# WirelessTallyReceiver.net
KiCad netlist of a schematic drawn in EAGLE
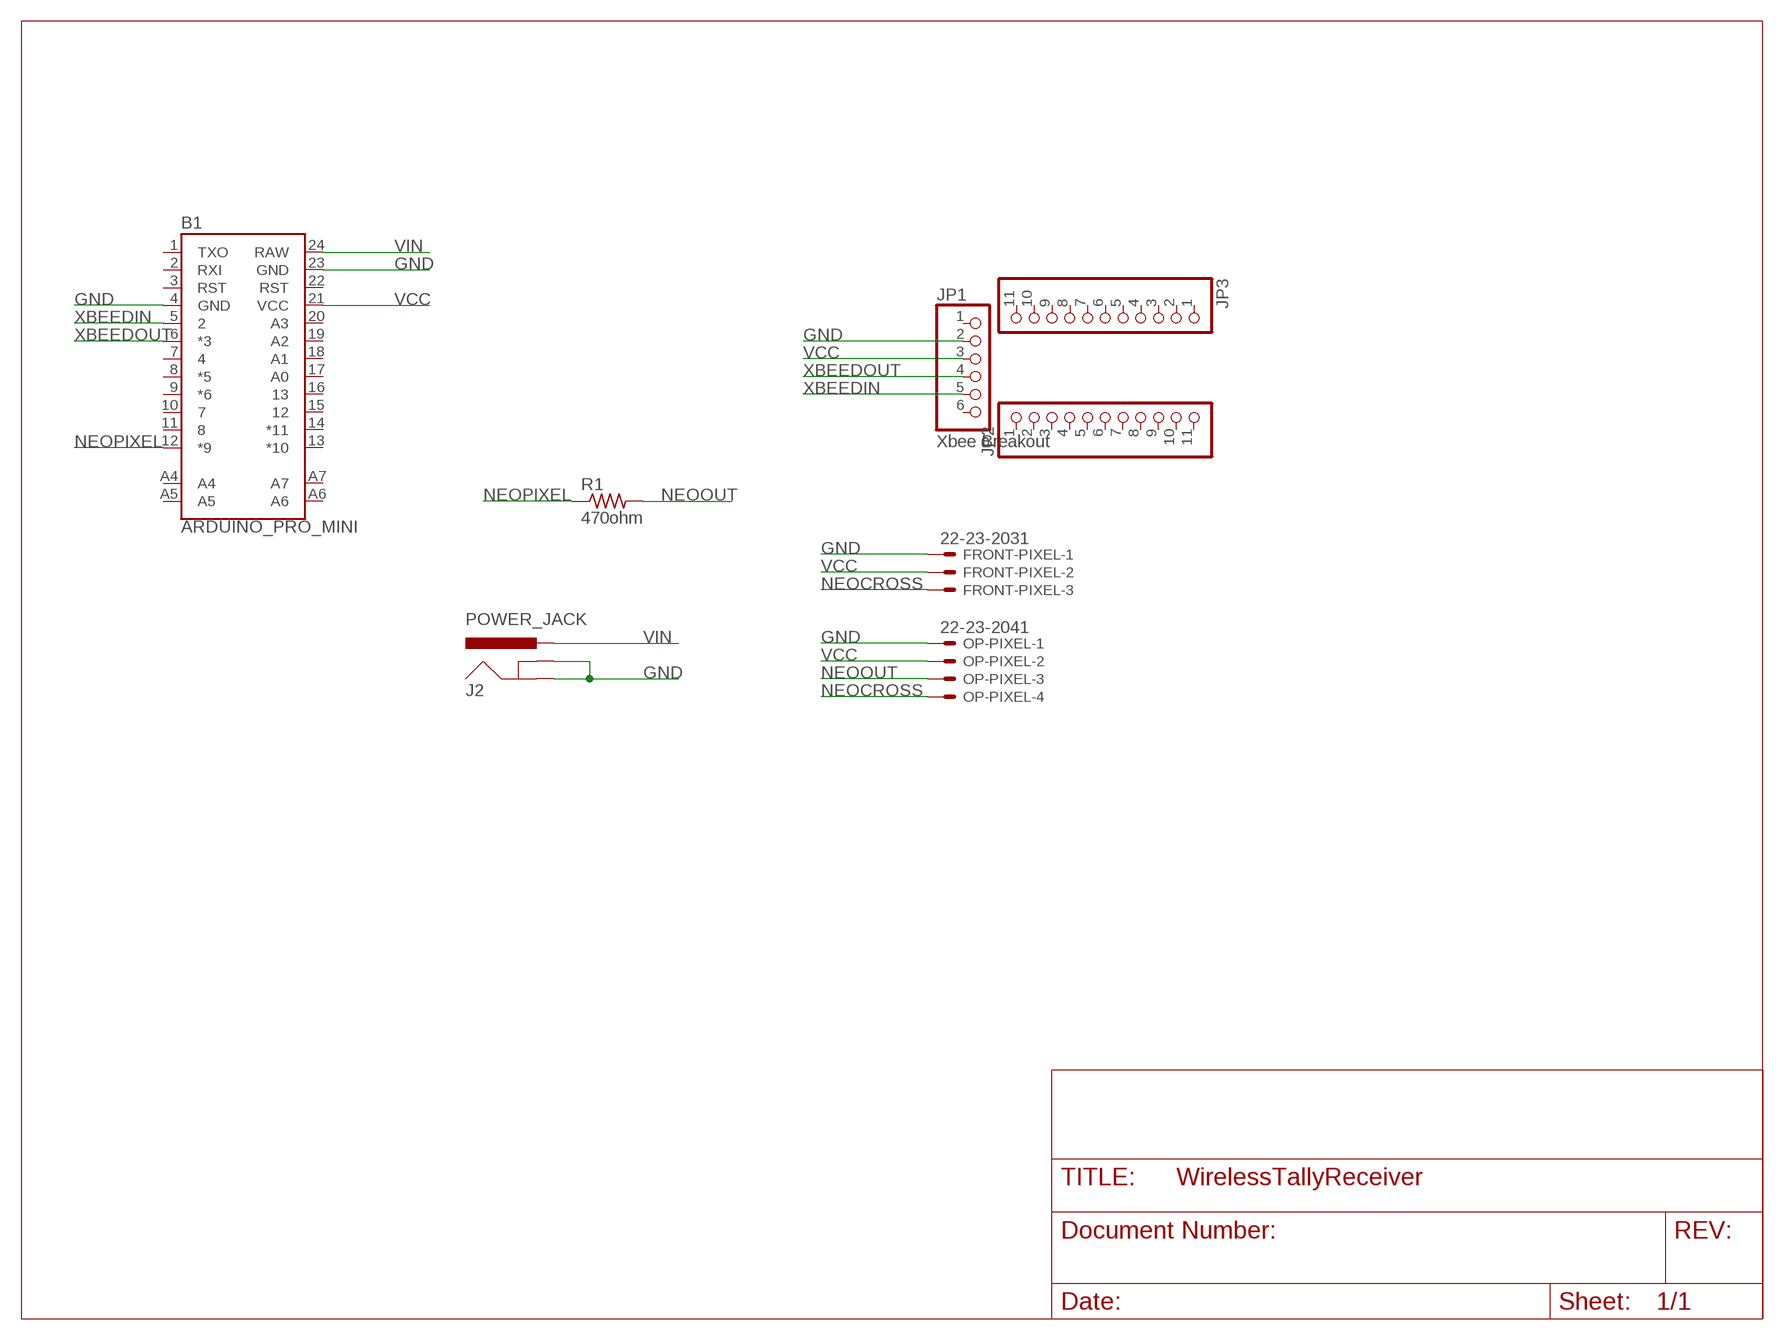
[diagram p0: schematic, sheet 1]

(export (version "E")
  (design (tool "Eeschema 10.0.6"))
  (components
    (comp (ref "B1")
      (value "ARDUINO_PRO_MINI")
      (footprint "eagle-import:ARDUINO_PRO_MINI")
      (libsource (lib "eagle-import") (part "ARDUINO_PRO_MINI"))
    )
    (comp (ref "FRONT-PIXEL")
      (value "22-23-2031")
      (footprint "eagle-import:22-23-2031")
      (fields (field (name "MF") "MOLEX"))
      (libsource (lib "eagle-import") (part "22-23-2031"))
    )
    (comp (ref "J2")
      (value "POWER_JACK")
      (footprint "eagle-import:POWER_JACK_PTH")
      (libsource (lib "eagle-import") (part "POWER_JACK"))
    )
    (comp (ref "JP1")
      (value "Xbee Breakout")
      (footprint "eagle-import:1X06")
      (libsource (lib "eagle-import") (part "PINHD-1X6"))
    )
    (comp (ref "JP2")
      (value "PINHD-1X11")
      (footprint "eagle-import:1X11")
      (libsource (lib "eagle-import") (part "PINHD-1X11"))
    )
    (comp (ref "JP3")
      (value "PINHD-1X11")
      (footprint "eagle-import:1X11")
      (libsource (lib "eagle-import") (part "PINHD-1X11"))
    )
    (comp (ref "OP-PIXEL")
      (value "22-23-2041")
      (footprint "eagle-import:22-23-2041")
      (fields (field (name "MF") "MOLEX"))
      (libsource (lib "eagle-import") (part "22-23-2041"))
    )
    (comp (ref "R1")
      (value "470ohm")
      (footprint "eagle-import:R0805")
      (libsource (lib "eagle-import") (part "R-US_R0805"))
    )
  )
  (nets
    (net (code "1") (name "/GND") (class "Default")
      (node (ref "B1") (pin "23") (pinfunction "GND_23") (pintype "power_in"))
      (node (ref "B1") (pin "4") (pinfunction "GND_4") (pintype "power_in"))
      (node (ref "FRONT-PIXEL") (pin "1") (pinfunction "S_1") (pintype "passive"))
      (node (ref "J2") (pin "GND") (pinfunction "GND_GND") (pintype "bidirectional"))
      (node (ref "J2") (pin "GNDBREAK") (pinfunction "GNDBREAK_GNDBREAK") (pintype "bidirectional"))
      (node (ref "JP1") (pin "2") (pinfunction "2_2") (pintype "passive"))
      (node (ref "OP-PIXEL") (pin "1") (pinfunction "S_1") (pintype "passive"))
    )
    (net (code "2") (name "/NEOCROSS") (class "Default")
      (node (ref "FRONT-PIXEL") (pin "3") (pinfunction "S_3") (pintype "passive"))
      (node (ref "OP-PIXEL") (pin "4") (pinfunction "S_4") (pintype "passive"))
    )
    (net (code "3") (name "/NEOOUT") (class "Default")
      (node (ref "OP-PIXEL") (pin "3") (pinfunction "S_3") (pintype "passive"))
      (node (ref "R1") (pin "2") (pinfunction "2_2") (pintype "passive"))
    )
    (net (code "4") (name "/NEOPIXEL") (class "Default")
      (node (ref "B1") (pin "12") (pinfunction "*9_12") (pintype "bidirectional"))
      (node (ref "R1") (pin "1") (pinfunction "1_1") (pintype "passive"))
    )
    (net (code "5") (name "/VCC") (class "Default")
      (node (ref "B1") (pin "21") (pinfunction "VCC_21") (pintype "power_in"))
      (node (ref "FRONT-PIXEL") (pin "2") (pinfunction "S_2") (pintype "passive"))
      (node (ref "JP1") (pin "3") (pinfunction "3_3") (pintype "passive"))
      (node (ref "OP-PIXEL") (pin "2") (pinfunction "S_2") (pintype "passive"))
    )
    (net (code "6") (name "/VIN") (class "Default")
      (node (ref "B1") (pin "24") (pinfunction "RAW_24") (pintype "power_in"))
      (node (ref "J2") (pin "PWR") (pinfunction "PWR_PWR") (pintype "bidirectional"))
    )
    (net (code "7") (name "/XBEEDIN") (class "Default")
      (node (ref "B1") (pin "5") (pinfunction "2_5") (pintype "bidirectional"))
      (node (ref "JP1") (pin "5") (pinfunction "5_5") (pintype "passive"))
    )
    (net (code "8") (name "/XBEEDOUT") (class "Default")
      (node (ref "B1") (pin "6") (pinfunction "*3_6") (pintype "bidirectional"))
      (node (ref "JP1") (pin "4") (pinfunction "4_4") (pintype "passive"))
    )
    (net (code "9") (name "unconnected-(B1-*5-Pad8)") (class "Default")
      (node (ref "B1") (pin "8") (pinfunction "*5_8") (pintype "bidirectional"))
    )
    (net (code "10") (name "unconnected-(B1-*6-Pad9)") (class "Default")
      (node (ref "B1") (pin "9") (pinfunction "*6_9") (pintype "bidirectional"))
    )
    (net (code "11") (name "unconnected-(B1-*10-Pad13)") (class "Default")
      (node (ref "B1") (pin "13") (pinfunction "*10_13") (pintype "bidirectional"))
    )
    (net (code "12") (name "unconnected-(B1-*11-Pad14)") (class "Default")
      (node (ref "B1") (pin "14") (pinfunction "*11_14") (pintype "bidirectional"))
    )
    (net (code "13") (name "unconnected-(B1-4-Pad7)") (class "Default")
      (node (ref "B1") (pin "7") (pinfunction "4_7") (pintype "bidirectional"))
    )
    (net (code "14") (name "unconnected-(B1-7-Pad10)") (class "Default")
      (node (ref "B1") (pin "10") (pinfunction "7_10") (pintype "bidirectional"))
    )
    (net (code "15") (name "unconnected-(B1-8-Pad11)") (class "Default")
      (node (ref "B1") (pin "11") (pinfunction "8_11") (pintype "bidirectional"))
    )
    (net (code "16") (name "unconnected-(B1-12-Pad15)") (class "Default")
      (node (ref "B1") (pin "15") (pinfunction "12_15") (pintype "bidirectional"))
    )
    (net (code "17") (name "unconnected-(B1-13-Pad16)") (class "Default")
      (node (ref "B1") (pin "16") (pinfunction "13_16") (pintype "bidirectional"))
    )
    (net (code "18") (name "unconnected-(B1-A0-Pad17)") (class "Default")
      (node (ref "B1") (pin "17") (pinfunction "A0_17") (pintype "bidirectional"))
    )
    (net (code "19") (name "unconnected-(B1-A1-Pad18)") (class "Default")
      (node (ref "B1") (pin "18") (pinfunction "A1_18") (pintype "bidirectional"))
    )
    (net (code "20") (name "unconnected-(B1-A2-Pad19)") (class "Default")
      (node (ref "B1") (pin "19") (pinfunction "A2_19") (pintype "bidirectional"))
    )
    (net (code "21") (name "unconnected-(B1-A3-Pad20)") (class "Default")
      (node (ref "B1") (pin "20") (pinfunction "A3_20") (pintype "bidirectional"))
    )
    (net (code "22") (name "unconnected-(B1-PadA4)") (class "Default")
      (node (ref "B1") (pin "A4") (pinfunction "A4_A4") (pintype "bidirectional"))
    )
    (net (code "23") (name "unconnected-(B1-PadA5)") (class "Default")
      (node (ref "B1") (pin "A5") (pinfunction "A5_A5") (pintype "bidirectional"))
    )
    (net (code "24") (name "unconnected-(B1-PadA6)") (class "Default")
      (node (ref "B1") (pin "A6") (pinfunction "A6_A6") (pintype "bidirectional"))
    )
    (net (code "25") (name "unconnected-(B1-PadA7)") (class "Default")
      (node (ref "B1") (pin "A7") (pinfunction "A7_A7") (pintype "bidirectional"))
    )
    (net (code "26") (name "unconnected-(B1-RST-Pad3)") (class "Default")
      (node (ref "B1") (pin "3") (pinfunction "RST_3") (pintype "bidirectional"))
    )
    (net (code "27") (name "unconnected-(B1-RST-Pad22)") (class "Default")
      (node (ref "B1") (pin "22") (pinfunction "RST_22") (pintype "bidirectional"))
    )
    (net (code "28") (name "unconnected-(B1-RXI-Pad2)") (class "Default")
      (node (ref "B1") (pin "2") (pinfunction "RXI_2") (pintype "bidirectional"))
    )
    (net (code "29") (name "unconnected-(B1-TXO-Pad1)") (class "Default")
      (node (ref "B1") (pin "1") (pinfunction "TXO_1") (pintype "bidirectional"))
    )
    (net (code "30") (name "unconnected-(JP1-Pad1)") (class "Default")
      (node (ref "JP1") (pin "1") (pinfunction "1_1") (pintype "passive"))
    )
    (net (code "31") (name "unconnected-(JP1-Pad6)") (class "Default")
      (node (ref "JP1") (pin "6") (pinfunction "6_6") (pintype "passive"))
    )
    (net (code "32") (name "unconnected-(JP2-Pad1)") (class "Default")
      (node (ref "JP2") (pin "1") (pinfunction "1_1") (pintype "passive"))
    )
    (net (code "33") (name "unconnected-(JP2-Pad2)") (class "Default")
      (node (ref "JP2") (pin "2") (pinfunction "2_2") (pintype "passive"))
    )
    (net (code "34") (name "unconnected-(JP2-Pad3)") (class "Default")
      (node (ref "JP2") (pin "3") (pinfunction "3_3") (pintype "passive"))
    )
    (net (code "35") (name "unconnected-(JP2-Pad4)") (class "Default")
      (node (ref "JP2") (pin "4") (pinfunction "4_4") (pintype "passive"))
    )
    (net (code "36") (name "unconnected-(JP2-Pad5)") (class "Default")
      (node (ref "JP2") (pin "5") (pinfunction "5_5") (pintype "passive"))
    )
    (net (code "37") (name "unconnected-(JP2-Pad6)") (class "Default")
      (node (ref "JP2") (pin "6") (pinfunction "6_6") (pintype "passive"))
    )
    (net (code "38") (name "unconnected-(JP2-Pad7)") (class "Default")
      (node (ref "JP2") (pin "7") (pinfunction "7_7") (pintype "passive"))
    )
    (net (code "39") (name "unconnected-(JP2-Pad8)") (class "Default")
      (node (ref "JP2") (pin "8") (pinfunction "8_8") (pintype "passive"))
    )
    (net (code "40") (name "unconnected-(JP2-Pad9)") (class "Default")
      (node (ref "JP2") (pin "9") (pinfunction "9_9") (pintype "passive"))
    )
    (net (code "41") (name "unconnected-(JP2-Pad10)") (class "Default")
      (node (ref "JP2") (pin "10") (pinfunction "10_10") (pintype "passive"))
    )
    (net (code "42") (name "unconnected-(JP2-Pad11)") (class "Default")
      (node (ref "JP2") (pin "11") (pinfunction "11_11") (pintype "passive"))
    )
    (net (code "43") (name "unconnected-(JP3-Pad1)") (class "Default")
      (node (ref "JP3") (pin "1") (pinfunction "1_1") (pintype "passive"))
    )
    (net (code "44") (name "unconnected-(JP3-Pad2)") (class "Default")
      (node (ref "JP3") (pin "2") (pinfunction "2_2") (pintype "passive"))
    )
    (net (code "45") (name "unconnected-(JP3-Pad3)") (class "Default")
      (node (ref "JP3") (pin "3") (pinfunction "3_3") (pintype "passive"))
    )
    (net (code "46") (name "unconnected-(JP3-Pad4)") (class "Default")
      (node (ref "JP3") (pin "4") (pinfunction "4_4") (pintype "passive"))
    )
    (net (code "47") (name "unconnected-(JP3-Pad5)") (class "Default")
      (node (ref "JP3") (pin "5") (pinfunction "5_5") (pintype "passive"))
    )
    (net (code "48") (name "unconnected-(JP3-Pad6)") (class "Default")
      (node (ref "JP3") (pin "6") (pinfunction "6_6") (pintype "passive"))
    )
    (net (code "49") (name "unconnected-(JP3-Pad7)") (class "Default")
      (node (ref "JP3") (pin "7") (pinfunction "7_7") (pintype "passive"))
    )
    (net (code "50") (name "unconnected-(JP3-Pad8)") (class "Default")
      (node (ref "JP3") (pin "8") (pinfunction "8_8") (pintype "passive"))
    )
    (net (code "51") (name "unconnected-(JP3-Pad9)") (class "Default")
      (node (ref "JP3") (pin "9") (pinfunction "9_9") (pintype "passive"))
    )
    (net (code "52") (name "unconnected-(JP3-Pad10)") (class "Default")
      (node (ref "JP3") (pin "10") (pinfunction "10_10") (pintype "passive"))
    )
    (net (code "53") (name "unconnected-(JP3-Pad11)") (class "Default")
      (node (ref "JP3") (pin "11") (pinfunction "11_11") (pintype "passive"))
    )
  )
)
